# Verzerrer.net
KiCad netlist of a schematic drawn in EAGLE
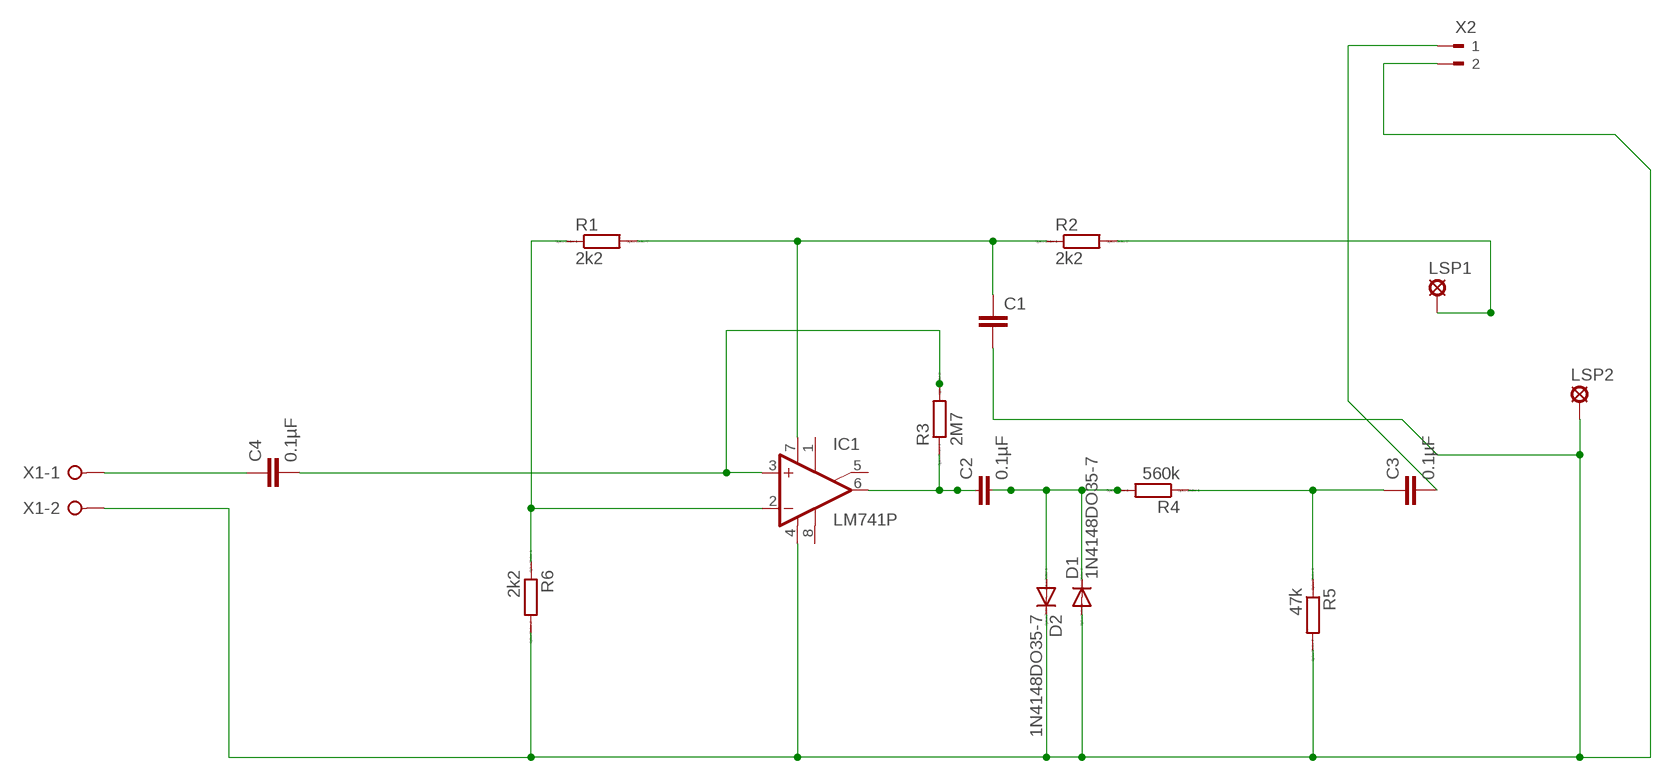
[diagram p0: schematic, sheet 1]

(export (version "E")
  (design (tool "Eeschema 10.0.6"))
  (components
    (comp (ref "C1")
      (value "C5/2.5")
      (footprint "eagle-import:C5B2.5")
      (libsource (lib "eagle-import") (part "C5/2.5"))
    )
    (comp (ref "C2")
      (value "0.1µF")
      (footprint "eagle-import:C5B2.5")
      (libsource (lib "eagle-import") (part "C5/2.5"))
    )
    (comp (ref "C3")
      (value "0.1µF")
      (footprint "eagle-import:C5B2.5")
      (libsource (lib "eagle-import") (part "C5/2.5"))
    )
    (comp (ref "C4")
      (value "0.1µF")
      (footprint "eagle-import:C5B2.5")
      (libsource (lib "eagle-import") (part "C5/2.5"))
    )
    (comp (ref "D1")
      (value "1N4148DO35-7")
      (footprint "eagle-import:DO35-7")
      (libsource (lib "eagle-import") (part "1N4148DO35-7"))
    )
    (comp (ref "D2")
      (value "1N4148DO35-7")
      (footprint "eagle-import:DO35-7")
      (libsource (lib "eagle-import") (part "1N4148DO35-7"))
    )
    (comp (ref "IC1")
      (value "LM741P")
      (footprint "eagle-import:DIL08")
      (libsource (lib "eagle-import") (part "741PLM"))
    )
    (comp (ref "LSP1")
      (value "LSP11")
      (footprint "eagle-import:LSP11")
      (libsource (lib "eagle-import") (part "LSP11"))
    )
    (comp (ref "LSP2")
      (value "LSP11")
      (footprint "eagle-import:LSP11")
      (libsource (lib "eagle-import") (part "LSP11"))
    )
    (comp (ref "R1")
      (value "2k2")
      (footprint "eagle-import:0207_10")
      (libsource (lib "eagle-import") (part "R0207/10"))
    )
    (comp (ref "R2")
      (value "2k2")
      (footprint "eagle-import:0207_10")
      (libsource (lib "eagle-import") (part "R0207/10"))
    )
    (comp (ref "R3")
      (value "2M7")
      (footprint "eagle-import:0207_10")
      (libsource (lib "eagle-import") (part "R0207/10"))
    )
    (comp (ref "R4")
      (value "560k")
      (footprint "eagle-import:0207_10")
      (libsource (lib "eagle-import") (part "R0207/10"))
    )
    (comp (ref "R5")
      (value "47k")
      (footprint "eagle-import:0207_10")
      (libsource (lib "eagle-import") (part "R0207/10"))
    )
    (comp (ref "R6")
      (value "2k2")
      (footprint "eagle-import:0207_10")
      (libsource (lib "eagle-import") (part "R0207/10"))
    )
    (comp (ref "X1")
      (value "W237-2N")
      (footprint "eagle-import:W237-2N")
      (libsource (lib "eagle-import") (part "W237-2N"))
    )
    (comp (ref "X2")
      (value "180-2")
      (footprint "eagle-import:180-2")
      (libsource (lib "eagle-import") (part "180-2"))
    )
  )
  (nets
    (net (code "1") (name "Net-(C2-Pad2)") (class "Default")
      (node (ref "C2") (pin "2") (pinfunction "2_2") (pintype "passive"))
      (node (ref "D1") (pin "C") (pinfunction "C_C") (pintype "passive"))
      (node (ref "D2") (pin "A") (pinfunction "A_A") (pintype "passive"))
      (node (ref "R4") (pin "2") (pinfunction "2_2") (pintype "passive"))
    )
    (net (code "2") (name "Net-(C3-Pad1)") (class "Default")
      (node (ref "C3") (pin "1") (pinfunction "1_1") (pintype "passive"))
      (node (ref "R4") (pin "1") (pinfunction "1_1") (pintype "passive"))
      (node (ref "R5") (pin "1") (pinfunction "1_1") (pintype "passive"))
    )
    (net (code "3") (name "Net-(C3-Pad2)") (class "Default")
      (node (ref "C3") (pin "2") (pinfunction "2_2") (pintype "passive"))
      (node (ref "X2") (pin "1") (pinfunction "1_1") (pintype "passive"))
    )
    (net (code "4") (name "Net-(IC1-+IN)") (class "Default")
      (node (ref "C4") (pin "2") (pinfunction "2_2") (pintype "passive"))
      (node (ref "IC1") (pin "3") (pinfunction "+IN_3") (pintype "input"))
      (node (ref "R3") (pin "2") (pinfunction "2_2") (pintype "passive"))
    )
    (net (code "5") (name "Net-(IC1--IN)") (class "Default")
      (node (ref "IC1") (pin "2") (pinfunction "-IN_2") (pintype "input"))
      (node (ref "R1") (pin "1") (pinfunction "1_1") (pintype "passive"))
      (node (ref "R6") (pin "1") (pinfunction "1_1") (pintype "passive"))
    )
    (net (code "6") (name "Net-(IC1-OUT)") (class "Default")
      (node (ref "C2") (pin "1") (pinfunction "1_1") (pintype "passive"))
      (node (ref "IC1") (pin "6") (pinfunction "OUT_6") (pintype "output"))
      (node (ref "R3") (pin "1") (pinfunction "1_1") (pintype "passive"))
    )
    (net (code "7") (name "Net-(IC1-V+)") (class "Default")
      (node (ref "C1") (pin "1") (pinfunction "1_1") (pintype "passive"))
      (node (ref "IC1") (pin "7") (pinfunction "V+_7") (pintype "power_in"))
      (node (ref "R1") (pin "2") (pinfunction "2_2") (pintype "passive"))
      (node (ref "R2") (pin "1") (pinfunction "1_1") (pintype "passive"))
    )
    (net (code "8") (name "Net-(IC1-V-)") (class "Default")
      (node (ref "C1") (pin "2") (pinfunction "2_2") (pintype "passive"))
      (node (ref "D1") (pin "A") (pinfunction "A_A") (pintype "passive"))
      (node (ref "D2") (pin "C") (pinfunction "C_C") (pintype "passive"))
      (node (ref "IC1") (pin "4") (pinfunction "V-_4") (pintype "power_in"))
      (node (ref "LSP2") (pin "MP") (pinfunction "MP_MP") (pintype "passive"))
      (node (ref "R5") (pin "2") (pinfunction "2_2") (pintype "passive"))
      (node (ref "R6") (pin "2") (pinfunction "2_2") (pintype "passive"))
      (node (ref "X1") (pin "2") (pinfunction "KL_2") (pintype "passive"))
      (node (ref "X2") (pin "2") (pinfunction "2_2") (pintype "passive"))
    )
    (net (code "9") (name "Net-(LSP1-PadMP)") (class "Default")
      (node (ref "LSP1") (pin "MP") (pinfunction "MP_MP") (pintype "passive"))
      (node (ref "R2") (pin "2") (pinfunction "2_2") (pintype "passive"))
    )
    (net (code "10") (name "Net-(X1A-KL)") (class "Default")
      (node (ref "C4") (pin "1") (pinfunction "1_1") (pintype "passive"))
      (node (ref "X1") (pin "1") (pinfunction "KL_1") (pintype "passive"))
    )
    (net (code "11") (name "unconnected-(IC1-ON1-Pad1)") (class "Default")
      (node (ref "IC1") (pin "1") (pinfunction "ON1_1") (pintype "passive"))
    )
    (net (code "12") (name "unconnected-(IC1-ON2-Pad5)") (class "Default")
      (node (ref "IC1") (pin "5") (pinfunction "ON2_5") (pintype "passive"))
    )
    (net (code "13") (name "unconnected-(IC1-OPT-Pad8)") (class "Default")
      (node (ref "IC1") (pin "8") (pinfunction "OPT_8") (pintype "passive"))
    )
  )
)
